# Compuertas_SCH.net
KiCad netlist of a schematic drawn in Altium Designer
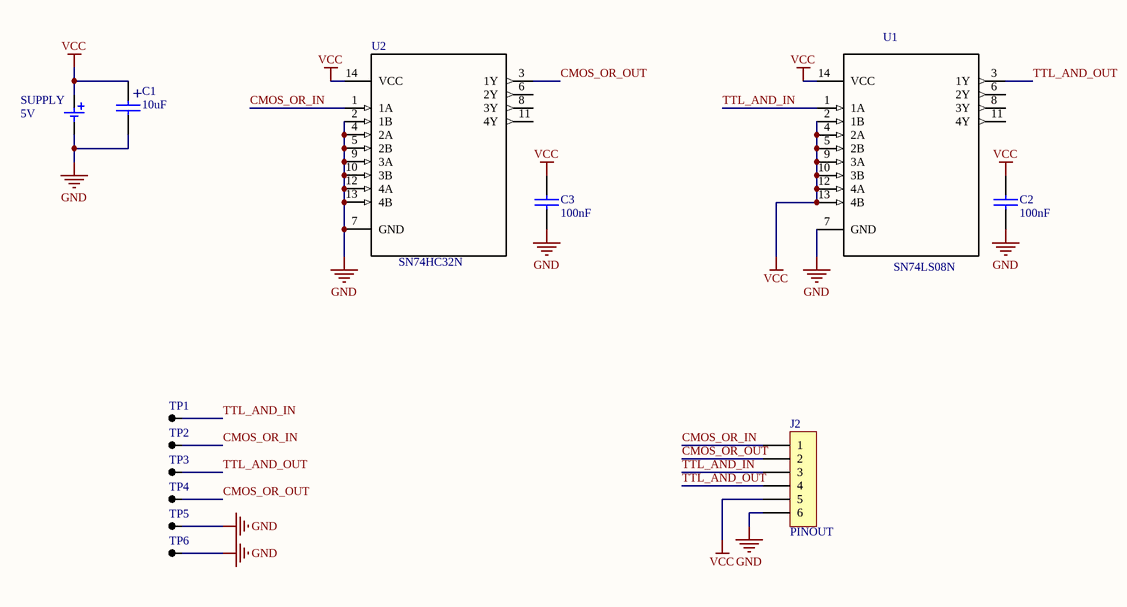
[diagram p0: Compuertas_SCH.SchDoc]

(export (version "E")
  (design (tool "Eeschema 10.0.6"))
  (components
    (comp (ref "C1") (value "10uF") (footprint "CAP100RP") (libsource (lib "LIBEBAL") (part "CAPPOL")))
    (comp (ref "C2") (value "100nF") (footprint "0805") (libsource (lib "LIBEBAL") (part "CAP")))
    (comp (ref "C3") (value "100nF") (footprint "0805") (libsource (lib "LIBEBAL") (part "CAP")))
    (comp (ref "J2") (value "PINOUT") (footprint "SIP6") (libsource (lib "LIBEBAL") (part "CON6")))
    (comp (ref "SUPPLY")
      (value "5V")
      (footprint "BORNERA2")
      (description "BATERIA")
      (libsource (lib "LIBEBAL") (part "BATERIA"))
    )
    (comp (ref "TP1") (value "TP") (footprint "TPTH") (libsource (lib "LIB PIO IX") (part "TP")))
    (comp (ref "TP2") (value "TP") (footprint "TPTH") (libsource (lib "LIB PIO IX") (part "TP")))
    (comp (ref "TP3") (value "TP") (footprint "TPTH") (libsource (lib "LIB PIO IX") (part "TP")))
    (comp (ref "TP4") (value "TP") (footprint "TPTH") (libsource (lib "LIB PIO IX") (part "TP")))
    (comp (ref "TP5") (value "TP") (footprint "TPTH") (libsource (lib "LIB PIO IX") (part "TP")))
    (comp (ref "TP6") (value "TP") (footprint "TPTH") (libsource (lib "LIB PIO IX") (part "TP")))
    (comp (ref "U1")
      (value "SN74LS08N")
      (footprint "*DIP254P762X508-14")
      (description "AND Gate 4 Element 2 Input Bipolar 14-Pin Plastic DIP Tube")
      (libsource (lib "SN74LS08N") (part "SN74LS08N"))
    )
    (comp (ref "U2")
      (value "SN74HC32N")
      (footprint "*DIP254P762X508-14")
      (description "IC: digital; Channels: 4; OR; Inputs: 2; THT; DIP14; Seri")
      (libsource (lib "SN74HC32N") (part "SN74HC32N"))
    )
  )
  (nets
    (net (code "1") (name "/CMOS_OR_IN") (class "Default")
      (node (ref "J2") (pin "1") (pinfunction "1_1") (pintype "passive"))
      (node (ref "TP2") (pin "1") (pinfunction "1_1") (pintype "passive"))
      (node (ref "U2") (pin "1") (pinfunction "1A_1") (pintype "input"))
    )
    (net (code "2") (name "/CMOS_OR_OUT") (class "Default")
      (node (ref "J2") (pin "2") (pinfunction "2_2") (pintype "passive"))
      (node (ref "TP4") (pin "1") (pinfunction "1_1") (pintype "passive"))
      (node (ref "U2") (pin "3") (pinfunction "1Y_3") (pintype "output"))
    )
    (net (code "3") (name "/TTL_AND_IN") (class "Default")
      (node (ref "J2") (pin "3") (pinfunction "3_3") (pintype "passive"))
      (node (ref "TP1") (pin "1") (pinfunction "1_1") (pintype "passive"))
      (node (ref "U1") (pin "1") (pinfunction "1A_1") (pintype "input"))
    )
    (net (code "4") (name "/TTL_AND_OUT") (class "Default")
      (node (ref "J2") (pin "4") (pinfunction "4_4") (pintype "passive"))
      (node (ref "TP3") (pin "1") (pinfunction "1_1") (pintype "passive"))
      (node (ref "U1") (pin "3") (pinfunction "1Y_3") (pintype "output"))
    )
    (net (code "5") (name "GND") (class "Default")
      (node (ref "C1") (pin "2") (pinfunction "2_2") (pintype "passive"))
      (node (ref "C2") (pin "2") (pinfunction "2_2") (pintype "passive"))
      (node (ref "C3") (pin "2") (pinfunction "2_2") (pintype "passive"))
      (node (ref "J2") (pin "6") (pinfunction "6_6") (pintype "passive"))
      (node (ref "SUPPLY") (pin "2") (pintype "passive"))
      (node (ref "TP5") (pin "1") (pinfunction "1_1") (pintype "passive"))
      (node (ref "TP6") (pin "1") (pinfunction "1_1") (pintype "passive"))
      (node (ref "U1") (pin "7") (pinfunction "GND_7") (pintype "passive"))
      (node (ref "U2") (pin "10") (pinfunction "3B_10") (pintype "input"))
      (node (ref "U2") (pin "12") (pinfunction "4A_12") (pintype "input"))
      (node (ref "U2") (pin "13") (pinfunction "4B_13") (pintype "input"))
      (node (ref "U2") (pin "2") (pinfunction "1B_2") (pintype "input"))
      (node (ref "U2") (pin "4") (pinfunction "2A_4") (pintype "input"))
      (node (ref "U2") (pin "5") (pinfunction "2B_5") (pintype "input"))
      (node (ref "U2") (pin "7") (pinfunction "GND_7") (pintype "passive"))
      (node (ref "U2") (pin "9") (pinfunction "3A_9") (pintype "input"))
    )
    (net (code "6") (name "VCC") (class "Default")
      (node (ref "C1") (pin "1") (pinfunction "1_1") (pintype "passive"))
      (node (ref "C2") (pin "1") (pinfunction "1_1") (pintype "passive"))
      (node (ref "C3") (pin "1") (pinfunction "1_1") (pintype "passive"))
      (node (ref "J2") (pin "5") (pinfunction "5_5") (pintype "passive"))
      (node (ref "SUPPLY") (pin "1") (pintype "passive"))
      (node (ref "U1") (pin "10") (pinfunction "3B_10") (pintype "input"))
      (node (ref "U1") (pin "12") (pinfunction "4A_12") (pintype "input"))
      (node (ref "U1") (pin "13") (pinfunction "4B_13") (pintype "input"))
      (node (ref "U1") (pin "14") (pinfunction "VCC_14") (pintype "power_in"))
      (node (ref "U1") (pin "2") (pinfunction "1B_2") (pintype "input"))
      (node (ref "U1") (pin "4") (pinfunction "2A_4") (pintype "input"))
      (node (ref "U1") (pin "5") (pinfunction "2B_5") (pintype "input"))
      (node (ref "U1") (pin "9") (pinfunction "3A_9") (pintype "input"))
      (node (ref "U2") (pin "14") (pinfunction "VCC_14") (pintype "power_in"))
    )
    (net (code "7") (name "unconnected-(U1-2Y-Pad6)") (class "Default")
      (node (ref "U1") (pin "6") (pinfunction "2Y_6") (pintype "output"))
    )
    (net (code "8") (name "unconnected-(U1-3Y-Pad8)") (class "Default")
      (node (ref "U1") (pin "8") (pinfunction "3Y_8") (pintype "output"))
    )
    (net (code "9") (name "unconnected-(U1-4Y-Pad11)") (class "Default")
      (node (ref "U1") (pin "11") (pinfunction "4Y_11") (pintype "output"))
    )
    (net (code "10") (name "unconnected-(U2-2Y-Pad6)") (class "Default")
      (node (ref "U2") (pin "6") (pinfunction "2Y_6") (pintype "output"))
    )
    (net (code "11") (name "unconnected-(U2-3Y-Pad8)") (class "Default")
      (node (ref "U2") (pin "8") (pinfunction "3Y_8") (pintype "output"))
    )
    (net (code "12") (name "unconnected-(U2-4Y-Pad11)") (class "Default")
      (node (ref "U2") (pin "11") (pinfunction "4Y_11") (pintype "output"))
    )
  )
)
